# slow_clock.net
KiCad netlist of a schematic drawn in EAGLE
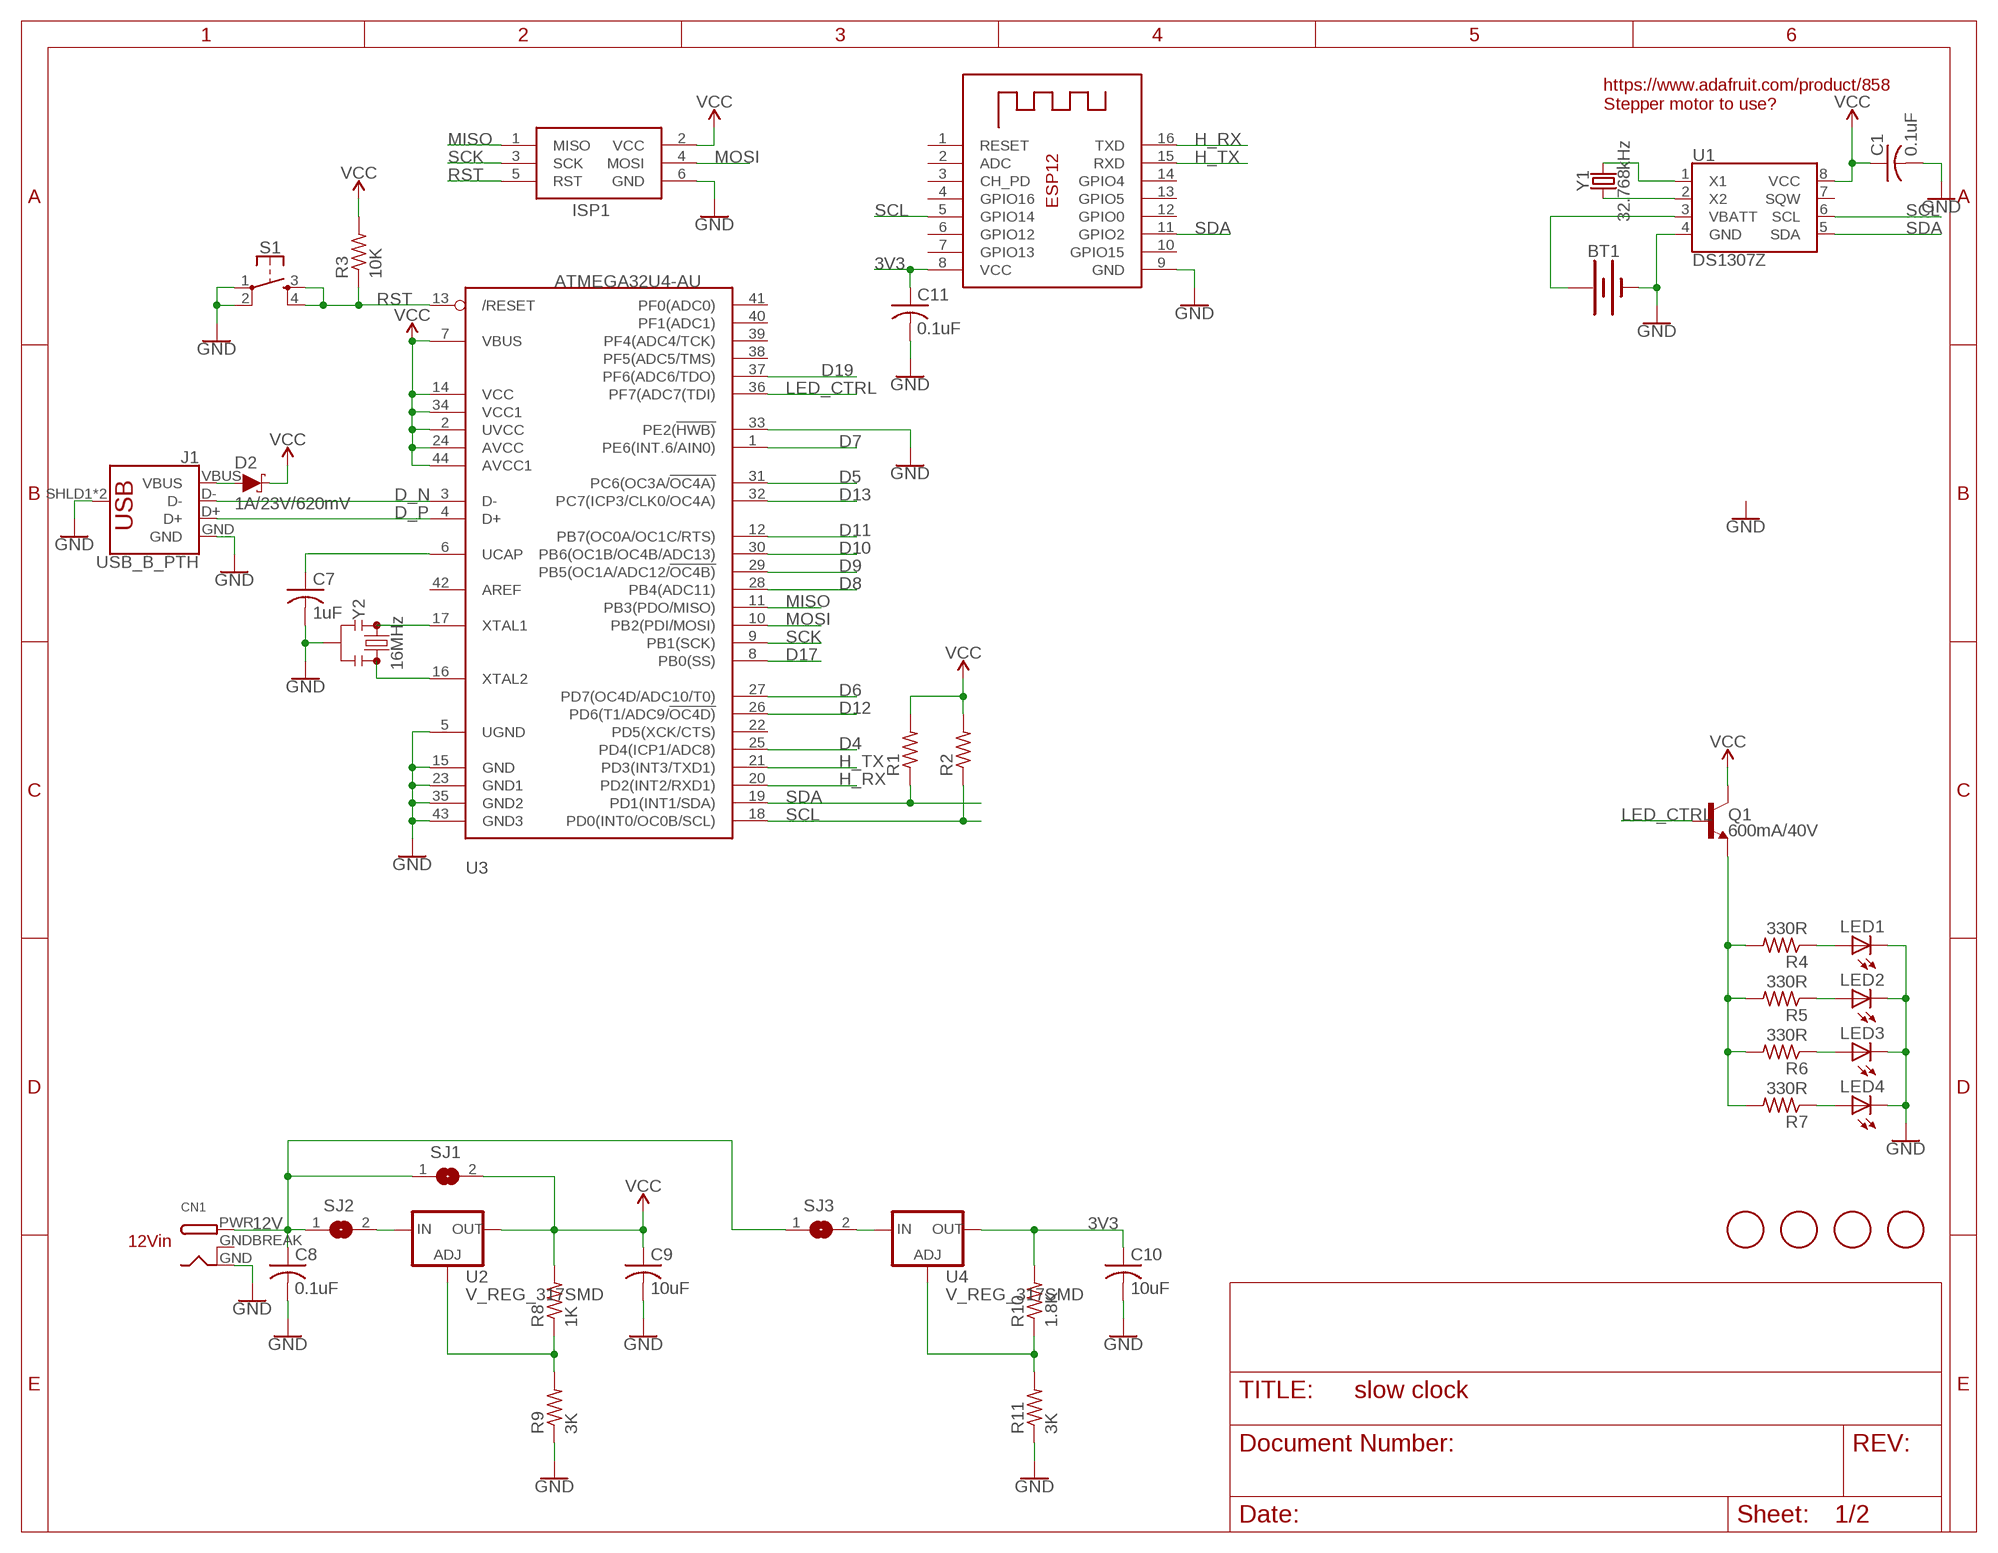
[diagram p0: schematic, sheet 1]
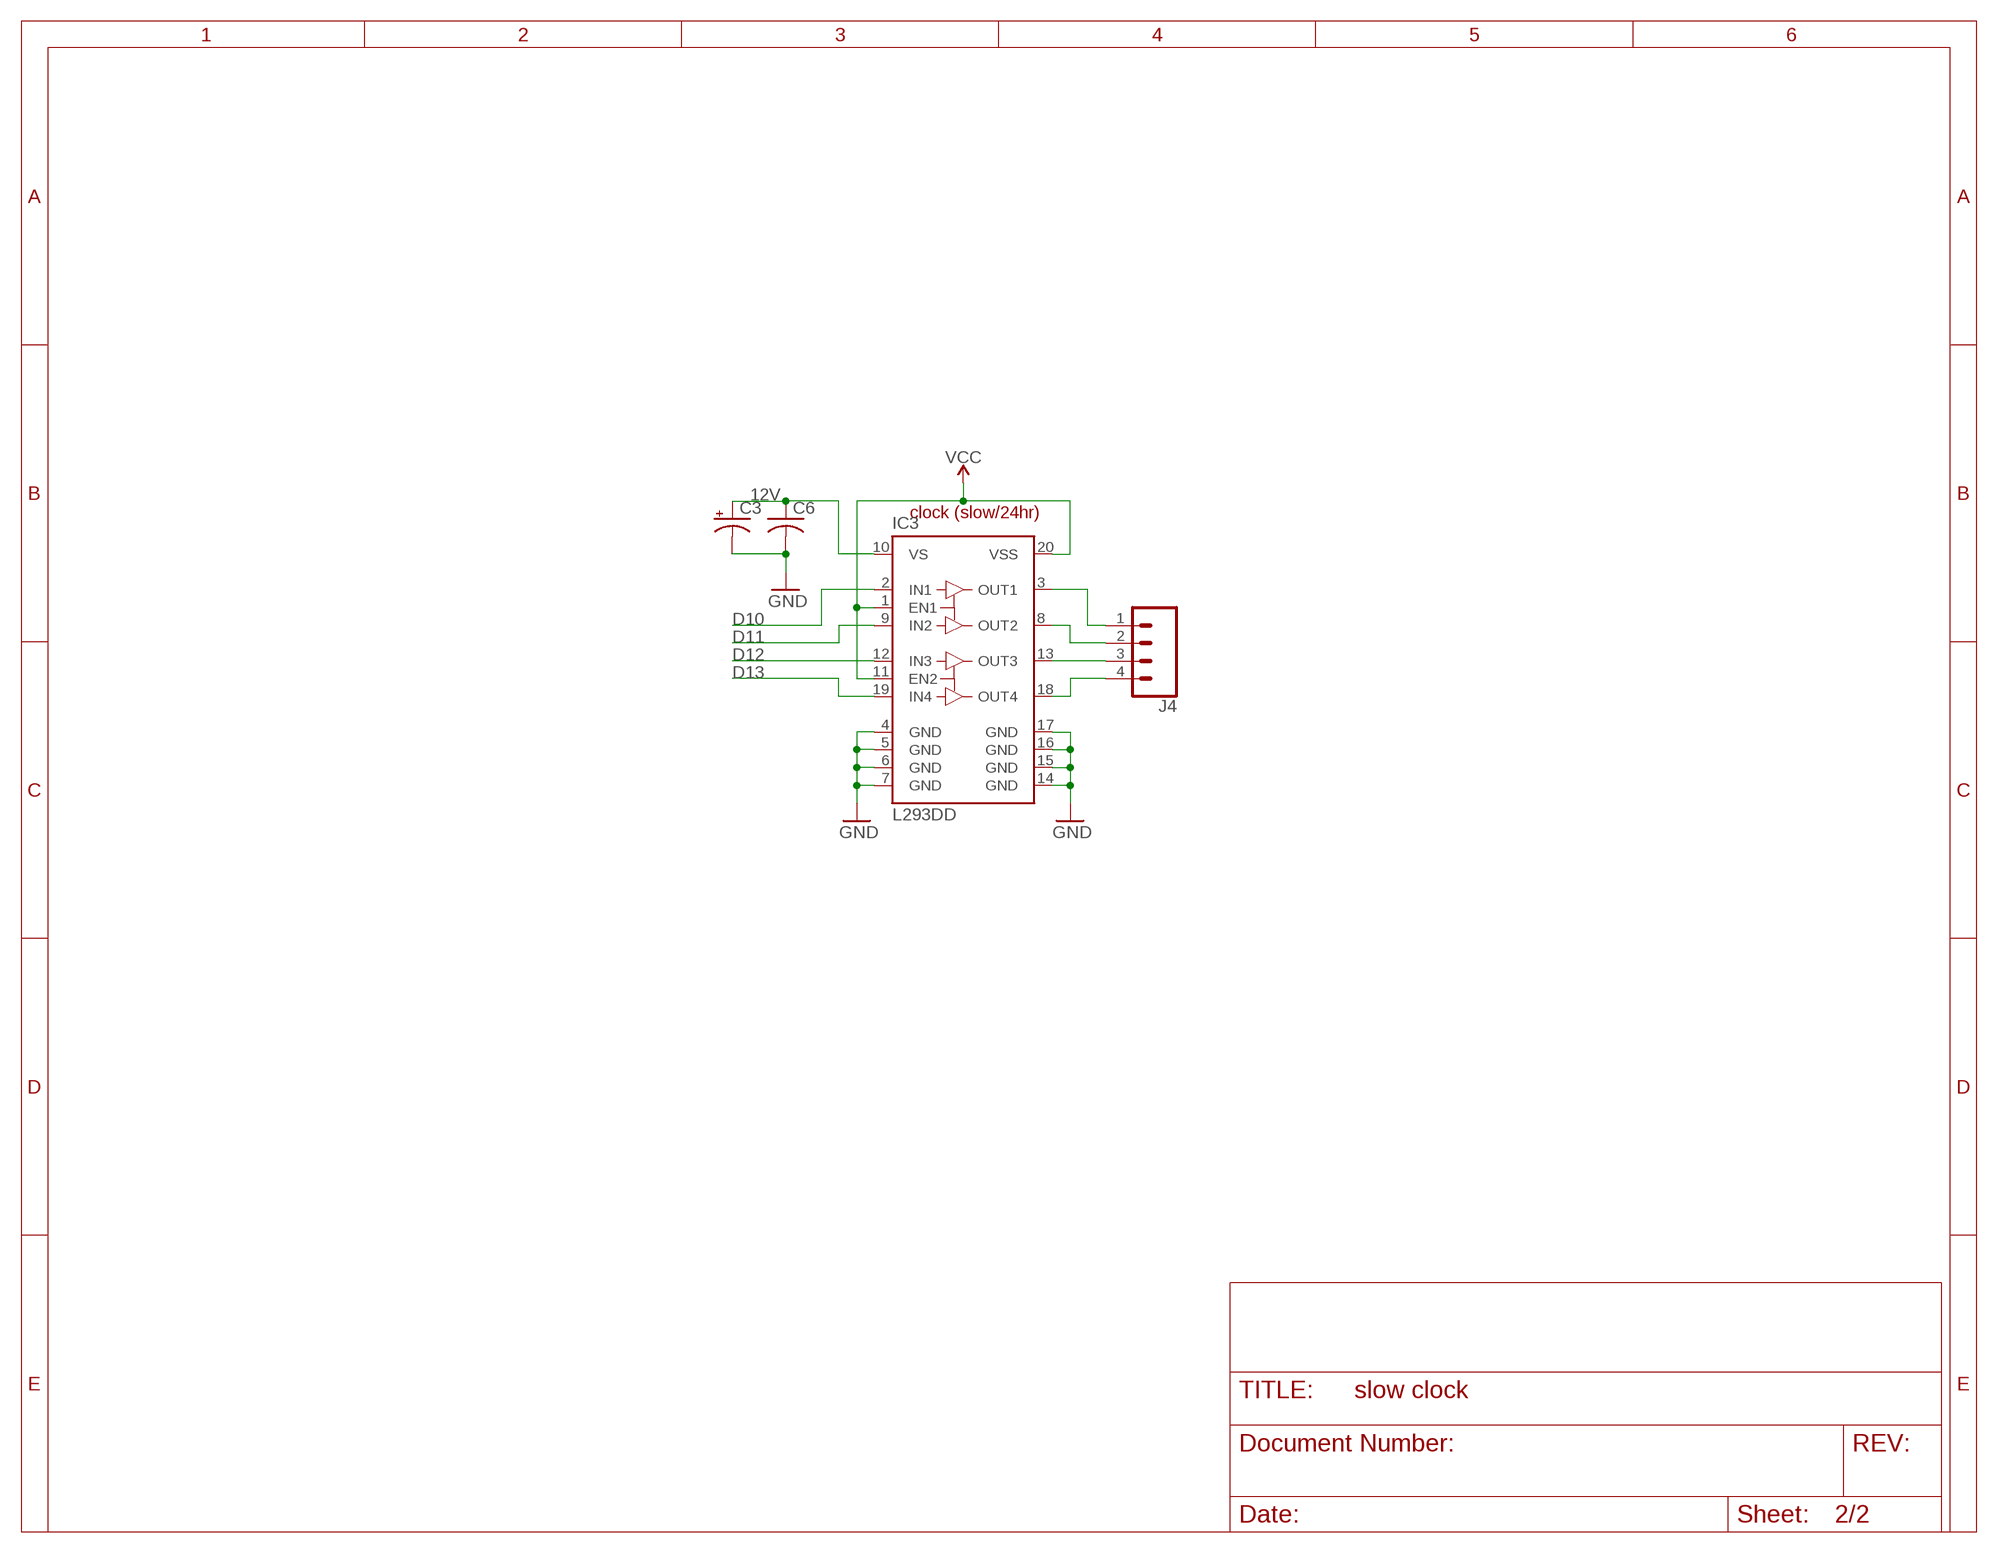
[diagram p1: schematic, sheet 2]

(export (version "E")
  (design (tool "Eeschema 10.0.6"))
  (components
    (comp (ref "C3")
      (value "CPOL-USD")
      (footprint "eagle-import:PANASONIC_D")
      (libsource (lib "eagle-import") (part "CPOL-USD"))
    )
    (comp (ref "C6")
      (value "C-USC0805")
      (footprint "eagle-import:C0805")
      (libsource (lib "eagle-import") (part "C-USC0805"))
    )
    (comp (ref "IC3")
      (value "L293DD")
      (footprint "eagle-import:SO20")
      (libsource (lib "eagle-import") (part "L293DD"))
    )
    (comp (ref "J4")
      (value "CONN_04LOCK")
      (footprint "eagle-import:1X04_LOCK")
      (libsource (lib "eagle-import") (part "CONN_04LOCK"))
    )
    (comp (ref "BT1")
      (value "BATTERY-12MM_SMD")
      (footprint "eagle-import:BATTCON_12MM")
      (libsource (lib "eagle-import") (part "BATTERY-12MM_SMD"))
    )
    (comp (ref "C1")
      (value "0.1uF")
      (footprint "eagle-import:C0805")
      (libsource (lib "eagle-import") (part "C-USC0805"))
    )
    (comp (ref "C7")
      (value "1uF")
      (footprint "eagle-import:C0805")
      (libsource (lib "eagle-import") (part "C-USC0805"))
    )
    (comp (ref "C8")
      (value "0.1uF")
      (footprint "eagle-import:C0805")
      (libsource (lib "eagle-import") (part "C-USC0805"))
    )
    (comp (ref "C9")
      (value "10uF")
      (footprint "eagle-import:C0805")
      (libsource (lib "eagle-import") (part "C-USC0805"))
    )
    (comp (ref "C10")
      (value "10uF")
      (footprint "eagle-import:C0805")
      (libsource (lib "eagle-import") (part "C-USC0805"))
    )
    (comp (ref "C11")
      (value "0.1uF")
      (footprint "eagle-import:C0805")
      (libsource (lib "eagle-import") (part "C-USC0805"))
    )
    (comp (ref "CN1")
      (value "DCBARRELPTH")
      (footprint "eagle-import:DCJACK_2MM_PTH")
      (libsource (lib "eagle-import") (part "DCBARRELPTH"))
    )
    (comp (ref "D2")
      (value "1A/23V/620mV")
      (footprint "eagle-import:SOD-323")
      (libsource (lib "eagle-import") (part "DIODE-SCHOTTKY-BAT20J"))
    )
    (comp (ref "ISP1")
      (value "AVRISP-6")
      (footprint "eagle-import:AVRISP")
      (libsource (lib "eagle-import") (part "AVRISP-6"))
    )
    (comp (ref "J1")
      (value "USB_B_PTH")
      (footprint "eagle-import:USB-B-PTH")
      (libsource (lib "eagle-import") (part "USB_B_PTH"))
    )
    (comp (ref "LED1")
      (value "LEDCHIPLED_0805")
      (footprint "eagle-import:CHIPLED_0805")
      (libsource (lib "eagle-import") (part "LEDCHIPLED_0805"))
    )
    (comp (ref "LED2")
      (value "LEDCHIPLED_0805")
      (footprint "eagle-import:CHIPLED_0805")
      (libsource (lib "eagle-import") (part "LEDCHIPLED_0805"))
    )
    (comp (ref "LED3")
      (value "LEDCHIPLED_0805")
      (footprint "eagle-import:CHIPLED_0805")
      (libsource (lib "eagle-import") (part "LEDCHIPLED_0805"))
    )
    (comp (ref "LED4")
      (value "LEDCHIPLED_0805")
      (footprint "eagle-import:CHIPLED_0805")
      (libsource (lib "eagle-import") (part "LEDCHIPLED_0805"))
    )
    (comp (ref "Q1")
      (value "600mA/40V")
      (footprint "eagle-import:SOT23-3")
      (libsource (lib "eagle-import") (part "TRANS_NPN-MMBT2222AL"))
    )
    (comp (ref "R1")
      (value "R-US_R0805")
      (footprint "eagle-import:R0805")
      (libsource (lib "eagle-import") (part "R-US_R0805"))
    )
    (comp (ref "R2")
      (value "R-US_R0805")
      (footprint "eagle-import:R0805")
      (libsource (lib "eagle-import") (part "R-US_R0805"))
    )
    (comp (ref "R3")
      (value "10K")
      (footprint "eagle-import:R0805")
      (libsource (lib "eagle-import") (part "R-US_R0805"))
    )
    (comp (ref "R4")
      (value "330R")
      (footprint "eagle-import:R0805")
      (libsource (lib "eagle-import") (part "R-US_R0805"))
    )
    (comp (ref "R5")
      (value "330R")
      (footprint "eagle-import:R0805")
      (libsource (lib "eagle-import") (part "R-US_R0805"))
    )
    (comp (ref "R6")
      (value "330R")
      (footprint "eagle-import:R0805")
      (libsource (lib "eagle-import") (part "R-US_R0805"))
    )
    (comp (ref "R7")
      (value "330R")
      (footprint "eagle-import:R0805")
      (libsource (lib "eagle-import") (part "R-US_R0805"))
    )
    (comp (ref "R8")
      (value "1K")
      (footprint "eagle-import:R0805")
      (libsource (lib "eagle-import") (part "R-US_R0805"))
    )
    (comp (ref "R9")
      (value "3K")
      (footprint "eagle-import:R0805")
      (libsource (lib "eagle-import") (part "R-US_R0805"))
    )
    (comp (ref "R10")
      (value "1.8K")
      (footprint "eagle-import:R0805")
      (libsource (lib "eagle-import") (part "R-US_R0805"))
    )
    (comp (ref "R11")
      (value "3K")
      (footprint "eagle-import:R0805")
      (libsource (lib "eagle-import") (part "R-US_R0805"))
    )
    (comp (ref "S1")
      (value "MOMENTARY-SWITCH-SPST-2-SMD-5.2MM")
      (footprint "eagle-import:TACTILE_SWITCH_SMD_5.2MM")
      (libsource (lib "eagle-import") (part "MOMENTARY-SWITCH-SPST-2-SMD-5.2MM"))
    )
    (comp (ref "SJ1") (value "SJ") (footprint "eagle-import:SJ") (libsource (lib "eagle-import") (part "SJ")))
    (comp (ref "SJ2") (value "SJ") (footprint "eagle-import:SJ") (libsource (lib "eagle-import") (part "SJ")))
    (comp (ref "SJ3") (value "SJ") (footprint "eagle-import:SJ") (libsource (lib "eagle-import") (part "SJ")))
    (comp (ref "U$2")
      (value "FIDUCIAL")
      (footprint "eagle-import:FIDUCIAL_1MM")
      (libsource (lib "eagle-import") (part "FIDUCIAL"))
    )
    (comp (ref "U$3")
      (value "FIDUCIAL")
      (footprint "eagle-import:FIDUCIAL_1MM")
      (libsource (lib "eagle-import") (part "FIDUCIAL"))
    )
    (comp (ref "U$4")
      (value "FIDUCIAL")
      (footprint "eagle-import:FIDUCIAL_1MM")
      (libsource (lib "eagle-import") (part "FIDUCIAL"))
    )
    (comp (ref "U$5")
      (value "FIDUCIAL")
      (footprint "eagle-import:FIDUCIAL_1MM")
      (libsource (lib "eagle-import") (part "FIDUCIAL"))
    )
    (comp (ref "U1")
      (value "DS1307Z")
      (footprint "eagle-import:SO08-0.15")
      (libsource (lib "eagle-import") (part "DS1307Z"))
    )
    (comp (ref "U2")
      (value "V_REG_317SMD")
      (footprint "eagle-import:SOT223")
      (libsource (lib "eagle-import") (part "V_REG_317SMD"))
    )
    (comp (ref "U3")
      (value "ATMEGA32U4-AU")
      (footprint "eagle-import:TQFP44")
      (libsource (lib "eagle-import") (part "ATMEGA32U4-AU"))
    )
    (comp (ref "U4")
      (value "V_REG_317SMD")
      (footprint "eagle-import:SOT223")
      (libsource (lib "eagle-import") (part "V_REG_317SMD"))
    )
    (comp (ref "X1")
      (value "ESP-12")
      (footprint "eagle-import:ESP-12")
      (libsource (lib "eagle-import") (part "ESP-12"))
    )
    (comp (ref "Y1")
      (value "32.768kHz")
      (footprint "eagle-import:CRYSTAL-PTH-2X6-CYL-KIT")
      (libsource (lib "eagle-import") (part "CRYSTAL-32.768KHZPTH-2X6-KIT"))
    )
    (comp (ref "Y2")
      (value "16MHz")
      (footprint "eagle-import:RESONATOR-SMD-3.2X1.3")
      (libsource (lib "eagle-import") (part "RESONATOR-16MHZSMD_3.2X1.3"))
    )
  )
  (nets
    (net (code "1") (name "3V3") (class "Default")
      (node (ref "C10") (pin "1") (pinfunction "1_1") (pintype "passive"))
      (node (ref "C11") (pin "1") (pinfunction "1_1") (pintype "passive"))
      (node (ref "R10") (pin "2") (pinfunction "2_2") (pintype "passive"))
      (node (ref "U4") (pin "2") (pinfunction "OUT_2") (pintype "output"))
      (node (ref "X1") (pin "8") (pinfunction "VCC_8") (pintype "power_in"))
    )
    (net (code "2") (name "12V") (class "Default")
      (node (ref "C3") (pin "+") (pinfunction "+_+") (pintype "passive"))
      (node (ref "C6") (pin "1") (pinfunction "1_1") (pintype "passive"))
      (node (ref "C8") (pin "1") (pinfunction "1_1") (pintype "passive"))
      (node (ref "CN1") (pin "PWR") (pinfunction "PWR_PWR") (pintype "power_in"))
      (node (ref "IC3") (pin "10") (pinfunction "VS_10") (pintype "power_in"))
      (node (ref "SJ1") (pin "1") (pinfunction "1_1") (pintype "passive"))
      (node (ref "SJ2") (pin "1") (pinfunction "1_1") (pintype "passive"))
      (node (ref "SJ3") (pin "1") (pinfunction "1_1") (pintype "passive"))
    )
    (net (code "3") (name "D4") (class "Default")
      (node (ref "U3") (pin "25") (pinfunction "PD4(ICP1/ADC8)_25") (pintype "bidirectional"))
    )
    (net (code "4") (name "D5") (class "Default")
      (node (ref "U3") (pin "31") (pinfunction "PC6(OC3A/~{OC4A})_31") (pintype "bidirectional"))
    )
    (net (code "5") (name "D6") (class "Default")
      (node (ref "U3") (pin "27") (pinfunction "PD7(OC4D/ADC10/T0)_27") (pintype "bidirectional"))
    )
    (net (code "6") (name "D7") (class "Default")
      (node (ref "U3") (pin "1") (pinfunction "PE6(INT.6/AIN0)_1") (pintype "bidirectional"))
    )
    (net (code "7") (name "D8") (class "Default")
      (node (ref "U3") (pin "28") (pinfunction "PB4(ADC11)_28") (pintype "bidirectional"))
    )
    (net (code "8") (name "D9") (class "Default")
      (node (ref "U3") (pin "29") (pinfunction "PB5(OC1A/ADC12/~{OC4B})_29") (pintype "bidirectional"))
    )
    (net (code "9") (name "D10") (class "Default")
      (node (ref "IC3") (pin "2") (pinfunction "IN1_2") (pintype "input"))
      (node (ref "U3") (pin "30") (pinfunction "PB6(OC1B/OC4B/ADC13)_30") (pintype "bidirectional"))
    )
    (net (code "10") (name "D11") (class "Default")
      (node (ref "IC3") (pin "9") (pinfunction "IN2_9") (pintype "input"))
      (node (ref "U3") (pin "12") (pinfunction "PB7(OC0A/OC1C/RTS)_12") (pintype "bidirectional"))
    )
    (net (code "11") (name "D12") (class "Default")
      (node (ref "IC3") (pin "12") (pinfunction "IN3_12") (pintype "input"))
      (node (ref "U3") (pin "26") (pinfunction "PD6(T1/ADC9/~{OC4D})_26") (pintype "bidirectional"))
    )
    (net (code "12") (name "D13") (class "Default")
      (node (ref "IC3") (pin "19") (pinfunction "IN4_19") (pintype "input"))
      (node (ref "U3") (pin "32") (pinfunction "PC7(ICP3/CLK0/OC4A)_32") (pintype "bidirectional"))
    )
    (net (code "13") (name "D17") (class "Default")
      (node (ref "U3") (pin "8") (pinfunction "PB0(SS)_8") (pintype "bidirectional"))
    )
    (net (code "14") (name "D19") (class "Default")
      (node (ref "U3") (pin "37") (pinfunction "PF6(ADC6/TDO)_37") (pintype "bidirectional"))
    )
    (net (code "15") (name "D_N") (class "Default")
      (node (ref "J1") (pin "D-") (pinfunction "D-_D-") (pintype "bidirectional"))
      (node (ref "U3") (pin "3") (pinfunction "D-_3") (pintype "bidirectional"))
    )
    (net (code "16") (name "D_P") (class "Default")
      (node (ref "J1") (pin "D+") (pinfunction "D+_D+") (pintype "bidirectional"))
      (node (ref "U3") (pin "4") (pinfunction "D+_4") (pintype "bidirectional"))
    )
    (net (code "17") (name "GND") (class "Default")
      (node (ref "BT1") (pin "GND") (pinfunction "-_GND") (pintype "power_in"))
      (node (ref "C1") (pin "2") (pinfunction "2_2") (pintype "passive"))
      (node (ref "C10") (pin "2") (pinfunction "2_2") (pintype "passive"))
      (node (ref "C11") (pin "2") (pinfunction "2_2") (pintype "passive"))
      (node (ref "C3") (pin "-") (pinfunction "-_-") (pintype "passive"))
      (node (ref "C6") (pin "2") (pinfunction "2_2") (pintype "passive"))
      (node (ref "C7") (pin "2") (pinfunction "2_2") (pintype "passive"))
      (node (ref "C8") (pin "2") (pinfunction "2_2") (pintype "passive"))
      (node (ref "C9") (pin "2") (pinfunction "2_2") (pintype "passive"))
      (node (ref "CN1") (pin "GND") (pinfunction "GND_GND") (pintype "power_in"))
      (node (ref "IC3") (pin "14") (pinfunction "GND_14") (pintype "power_in"))
      (node (ref "IC3") (pin "15") (pinfunction "GND_15") (pintype "power_in"))
      (node (ref "IC3") (pin "16") (pinfunction "GND_16") (pintype "power_in"))
      (node (ref "IC3") (pin "17") (pinfunction "GND_17") (pintype "power_in"))
      (node (ref "IC3") (pin "4") (pinfunction "GND_4") (pintype "power_in"))
      (node (ref "IC3") (pin "5") (pinfunction "GND_5") (pintype "power_in"))
      (node (ref "IC3") (pin "6") (pinfunction "GND_6") (pintype "power_in"))
      (node (ref "IC3") (pin "7") (pinfunction "GND_7") (pintype "power_in"))
      (node (ref "ISP1") (pin "6") (pinfunction "GND_6") (pintype "power_in"))
      (node (ref "J1") (pin "GND") (pinfunction "GND_GND") (pintype "power_in"))
      (node (ref "J1") (pin "SHLD1") (pinfunction "SHIELD_SHLD1") (pintype "bidirectional"))
      (node (ref "J1") (pin "SHLD2") (pinfunction "SHIELD_SHLD2") (pintype "bidirectional"))
      (node (ref "LED1") (pin "C") (pinfunction "C_C") (pintype "passive"))
      (node (ref "LED2") (pin "C") (pinfunction "C_C") (pintype "passive"))
      (node (ref "LED3") (pin "C") (pinfunction "C_C") (pintype "passive"))
      (node (ref "LED4") (pin "C") (pinfunction "C_C") (pintype "passive"))
      (node (ref "R11") (pin "1") (pinfunction "1_1") (pintype "passive"))
      (node (ref "R9") (pin "1") (pinfunction "1_1") (pintype "passive"))
      (node (ref "S1") (pin "1") (pinfunction "1_1") (pintype "passive"))
      (node (ref "S1") (pin "2") (pinfunction "2_2") (pintype "passive"))
      (node (ref "U1") (pin "4") (pinfunction "GND_4") (pintype "bidirectional"))
      (node (ref "U3") (pin "15") (pinfunction "GND_15") (pintype "bidirectional"))
      (node (ref "U3") (pin "23") (pinfunction "GND1_23") (pintype "bidirectional"))
      (node (ref "U3") (pin "33") (pinfunction "PE2(~{HWB})_33") (pintype "bidirectional"))
      (node (ref "U3") (pin "35") (pinfunction "GND2_35") (pintype "bidirectional"))
      (node (ref "U3") (pin "43") (pinfunction "GND3_43") (pintype "bidirectional"))
      (node (ref "U3") (pin "5") (pinfunction "UGND_5") (pintype "bidirectional"))
      (node (ref "X1") (pin "9") (pinfunction "GND_9") (pintype "power_in"))
      (node (ref "Y2") (pin "2") (pinfunction "2_2") (pintype "passive"))
    )
    (net (code "18") (name "GNDBREAK") (class "Default")
      (node (ref "CN1") (pin "GNDBREAK") (pinfunction "GNDBREAK_GNDBREAK") (pintype "power_in"))
    )
    (net (code "19") (name "H_RX") (class "Default")
      (node (ref "U3") (pin "20") (pinfunction "PD2(INT2/RXD1)_20") (pintype "bidirectional"))
      (node (ref "X1") (pin "16") (pinfunction "TXD_16") (pintype "output"))
    )
    (net (code "20") (name "H_TX") (class "Default")
      (node (ref "U3") (pin "21") (pinfunction "PD3(INT3/TXD1)_21") (pintype "bidirectional"))
      (node (ref "X1") (pin "15") (pinfunction "RXD_15") (pintype "input"))
    )
    (net (code "21") (name "LED_CTRL") (class "Default")
      (node (ref "Q1") (pin "1") (pinfunction "B_1") (pintype "passive"))
      (node (ref "U3") (pin "36") (pinfunction "PF7(ADC7(TDI)_36") (pintype "bidirectional"))
    )
    (net (code "22") (name "MISO") (class "Default")
      (node (ref "ISP1") (pin "1") (pinfunction "MISO_1") (pintype "input"))
      (node (ref "U3") (pin "11") (pinfunction "PB3(PDO/MISO)_11") (pintype "bidirectional"))
    )
    (net (code "23") (name "MOSI") (class "Default")
      (node (ref "ISP1") (pin "4") (pinfunction "MOSI_4") (pintype "output"))
      (node (ref "U3") (pin "10") (pinfunction "PB2(PDI/MOSI)_10") (pintype "bidirectional"))
    )
    (net (code "24") (name "Net-(BT1-+)") (class "Default")
      (node (ref "BT1") (pin "PWR@1") (pinfunction "+_PWR@1") (pintype "power_in"))
      (node (ref "U1") (pin "3") (pinfunction "VBATT_3") (pintype "bidirectional"))
    )
    (net (code "25") (name "Net-(D2-PadA)") (class "Default")
      (node (ref "D2") (pin "A") (pinfunction "A_A") (pintype "passive"))
      (node (ref "J1") (pin "VBUS") (pinfunction "VBUS_VBUS") (pintype "power_in"))
    )
    (net (code "26") (name "Net-(IC3-OUT1)") (class "Default")
      (node (ref "IC3") (pin "3") (pinfunction "OUT1_3") (pintype "output"))
      (node (ref "J4") (pin "1") (pinfunction "1_1") (pintype "passive"))
    )
    (net (code "27") (name "Net-(IC3-OUT2)") (class "Default")
      (node (ref "IC3") (pin "8") (pinfunction "OUT2_8") (pintype "output"))
      (node (ref "J4") (pin "2") (pinfunction "2_2") (pintype "passive"))
    )
    (net (code "28") (name "Net-(IC3-OUT3)") (class "Default")
      (node (ref "IC3") (pin "13") (pinfunction "OUT3_13") (pintype "output"))
      (node (ref "J4") (pin "3") (pinfunction "3_3") (pintype "passive"))
    )
    (net (code "29") (name "Net-(IC3-OUT4)") (class "Default")
      (node (ref "IC3") (pin "18") (pinfunction "OUT4_18") (pintype "output"))
      (node (ref "J4") (pin "4") (pinfunction "4_4") (pintype "passive"))
    )
    (net (code "30") (name "Net-(LED1-PadA)") (class "Default")
      (node (ref "LED1") (pin "A") (pinfunction "A_A") (pintype "passive"))
      (node (ref "R4") (pin "1") (pinfunction "1_1") (pintype "passive"))
    )
    (net (code "31") (name "Net-(LED2-PadA)") (class "Default")
      (node (ref "LED2") (pin "A") (pinfunction "A_A") (pintype "passive"))
      (node (ref "R5") (pin "1") (pinfunction "1_1") (pintype "passive"))
    )
    (net (code "32") (name "Net-(LED3-PadA)") (class "Default")
      (node (ref "LED3") (pin "A") (pinfunction "A_A") (pintype "passive"))
      (node (ref "R6") (pin "1") (pinfunction "1_1") (pintype "passive"))
    )
    (net (code "33") (name "Net-(LED4-PadA)") (class "Default")
      (node (ref "LED4") (pin "A") (pinfunction "A_A") (pintype "passive"))
      (node (ref "R7") (pin "1") (pinfunction "1_1") (pintype "passive"))
    )
    (net (code "34") (name "Net-(Q1-E)") (class "Default")
      (node (ref "Q1") (pin "2") (pinfunction "E_2") (pintype "passive"))
      (node (ref "R4") (pin "2") (pinfunction "2_2") (pintype "passive"))
      (node (ref "R5") (pin "2") (pinfunction "2_2") (pintype "passive"))
      (node (ref "R6") (pin "2") (pinfunction "2_2") (pintype "passive"))
      (node (ref "R7") (pin "2") (pinfunction "2_2") (pintype "passive"))
    )
    (net (code "35") (name "Net-(U1-X1)") (class "Default")
      (node (ref "U1") (pin "1") (pinfunction "X1_1") (pintype "bidirectional"))
      (node (ref "Y1") (pin "2") (pinfunction "2_2") (pintype "passive"))
    )
    (net (code "36") (name "Net-(U1-X2)") (class "Default")
      (node (ref "U1") (pin "2") (pinfunction "X2_2") (pintype "bidirectional"))
      (node (ref "Y1") (pin "1") (pinfunction "1_1") (pintype "passive"))
    )
    (net (code "37") (name "Net-(U2-ADJ)") (class "Default")
      (node (ref "R8") (pin "1") (pinfunction "1_1") (pintype "passive"))
      (node (ref "R9") (pin "2") (pinfunction "2_2") (pintype "passive"))
      (node (ref "U2") (pin "1") (pinfunction "ADJ_1") (pintype "input"))
    )
    (net (code "38") (name "Net-(U2-IN)") (class "Default")
      (node (ref "SJ2") (pin "2") (pinfunction "2_2") (pintype "passive"))
      (node (ref "U2") (pin "3") (pinfunction "IN_3") (pintype "input"))
    )
    (net (code "39") (name "Net-(U3-UCAP)") (class "Default")
      (node (ref "C7") (pin "1") (pinfunction "1_1") (pintype "passive"))
      (node (ref "U3") (pin "6") (pinfunction "UCAP_6") (pintype "bidirectional"))
    )
    (net (code "40") (name "Net-(U3-XTAL1)") (class "Default")
      (node (ref "U3") (pin "17") (pinfunction "XTAL1_17") (pintype "bidirectional"))
      (node (ref "Y2") (pin "1") (pinfunction "1_1") (pintype "passive"))
    )
    (net (code "41") (name "Net-(U3-XTAL2)") (class "Default")
      (node (ref "U3") (pin "16") (pinfunction "XTAL2_16") (pintype "bidirectional"))
      (node (ref "Y2") (pin "3") (pinfunction "3_3") (pintype "passive"))
    )
    (net (code "42") (name "Net-(U4-ADJ)") (class "Default")
      (node (ref "R10") (pin "1") (pinfunction "1_1") (pintype "passive"))
      (node (ref "R11") (pin "2") (pinfunction "2_2") (pintype "passive"))
      (node (ref "U4") (pin "1") (pinfunction "ADJ_1") (pintype "input"))
    )
    (net (code "43") (name "Net-(U4-IN)") (class "Default")
      (node (ref "SJ3") (pin "2") (pinfunction "2_2") (pintype "passive"))
      (node (ref "U4") (pin "3") (pinfunction "IN_3") (pintype "input"))
    )
    (net (code "44") (name "RST") (class "Default")
      (node (ref "ISP1") (pin "5") (pinfunction "RST_5") (pintype "output"))
      (node (ref "R3") (pin "1") (pinfunction "1_1") (pintype "passive"))
      (node (ref "S1") (pin "3") (pinfunction "3_3") (pintype "passive"))
      (node (ref "S1") (pin "4") (pinfunction "4_4") (pintype "passive"))
      (node (ref "U3") (pin "13") (pinfunction "/RESET_13") (pintype "bidirectional"))
    )
    (net (code "45") (name "SCK") (class "Default")
      (node (ref "ISP1") (pin "3") (pinfunction "SCK_3") (pintype "output"))
      (node (ref "U3") (pin "9") (pinfunction "PB1(SCK)_9") (pintype "bidirectional"))
    )
    (net (code "46") (name "SCL") (class "Default")
      (node (ref "R2") (pin "1") (pinfunction "1_1") (pintype "passive"))
      (node (ref "U1") (pin "6") (pinfunction "SCL_6") (pintype "bidirectional"))
      (node (ref "U3") (pin "18") (pinfunction "PD0(INT0/OC0B/SCL)_18") (pintype "bidirectional"))
      (node (ref "X1") (pin "5") (pinfunction "GPIO14_5") (pintype "bidirectional"))
    )
    (net (code "47") (name "SDA") (class "Default")
      (node (ref "R1") (pin "1") (pinfunction "1_1") (pintype "passive"))
      (node (ref "U1") (pin "5") (pinfunction "SDA_5") (pintype "bidirectional"))
      (node (ref "U3") (pin "19") (pinfunction "PD1(INT1/SDA)_19") (pintype "bidirectional"))
      (node (ref "X1") (pin "11") (pinfunction "GPIO2_11") (pintype "bidirectional"))
    )
    (net (code "48") (name "VCC") (class "Default")
      (node (ref "C1") (pin "1") (pinfunction "1_1") (pintype "passive"))
      (node (ref "C9") (pin "1") (pinfunction "1_1") (pintype "passive"))
      (node (ref "D2") (pin "C") (pinfunction "C_C") (pintype "passive"))
      (node (ref "IC3") (pin "1") (pinfunction "EN1_1") (pintype "input"))
      (node (ref "IC3") (pin "11") (pinfunction "EN2_11") (pintype "input"))
      (node (ref "IC3") (pin "20") (pinfunction "VSS_20") (pintype "power_in"))
      (node (ref "ISP1") (pin "2") (pinfunction "VCC_2") (pintype "power_in"))
      (node (ref "Q1") (pin "3") (pinfunction "C_3") (pintype "passive"))
      (node (ref "R1") (pin "2") (pinfunction "2_2") (pintype "passive"))
      (node (ref "R2") (pin "2") (pinfunction "2_2") (pintype "passive"))
      (node (ref "R3") (pin "2") (pinfunction "2_2") (pintype "passive"))
      (node (ref "R8") (pin "2") (pinfunction "2_2") (pintype "passive"))
      (node (ref "SJ1") (pin "2") (pinfunction "2_2") (pintype "passive"))
      (node (ref "U1") (pin "8") (pinfunction "VCC_8") (pintype "bidirectional"))
      (node (ref "U2") (pin "2") (pinfunction "OUT_2") (pintype "output"))
      (node (ref "U3") (pin "14") (pinfunction "VCC_14") (pintype "bidirectional"))
      (node (ref "U3") (pin "2") (pinfunction "UVCC_2") (pintype "bidirectional"))
      (node (ref "U3") (pin "24") (pinfunction "AVCC_24") (pintype "bidirectional"))
      (node (ref "U3") (pin "34") (pinfunction "VCC1_34") (pintype "bidirectional"))
      (node (ref "U3") (pin "44") (pinfunction "AVCC1_44") (pintype "bidirectional"))
      (node (ref "U3") (pin "7") (pinfunction "VBUS_7") (pintype "bidirectional"))
    )
    (net (code "49") (name "unconnected-(U1-SQW-Pad7)") (class "Default")
      (node (ref "U1") (pin "7") (pinfunction "SQW_7") (pintype "bidirectional"))
    )
    (net (code "50") (name "unconnected-(U3-AREF-Pad42)") (class "Default")
      (node (ref "U3") (pin "42") (pinfunction "AREF_42") (pintype "bidirectional"))
    )
    (net (code "51") (name "unconnected-(U3-PD5(XCK{slash}CTS)-Pad22)") (class "Default")
      (node (ref "U3") (pin "22") (pinfunction "PD5(XCK/CTS)_22") (pintype "bidirectional"))
    )
    (net (code "52") (name "unconnected-(U3-PF0(ADC0)-Pad41)") (class "Default")
      (node (ref "U3") (pin "41") (pinfunction "PF0(ADC0)_41") (pintype "bidirectional"))
    )
    (net (code "53") (name "unconnected-(U3-PF1(ADC1)-Pad40)") (class "Default")
      (node (ref "U3") (pin "40") (pinfunction "PF1(ADC1)_40") (pintype "bidirectional"))
    )
    (net (code "54") (name "unconnected-(U3-PF4(ADC4{slash}TCK)-Pad39)") (class "Default")
      (node (ref "U3") (pin "39") (pinfunction "PF4(ADC4/TCK)_39") (pintype "bidirectional"))
    )
    (net (code "55") (name "unconnected-(U3-PF5(ADC5{slash}TMS)-Pad38)") (class "Default")
      (node (ref "U3") (pin "38") (pinfunction "PF5(ADC5/TMS)_38") (pintype "bidirectional"))
    )
    (net (code "56") (name "unconnected-(X1-ADC-Pad2)") (class "Default")
      (node (ref "X1") (pin "2") (pinfunction "ADC_2") (pintype "passive"))
    )
    (net (code "57") (name "unconnected-(X1-CH_PD-Pad3)") (class "Default")
      (node (ref "X1") (pin "3") (pinfunction "CH_PD_3") (pintype "input"))
    )
    (net (code "58") (name "unconnected-(X1-GPIO0-Pad12)") (class "Default")
      (node (ref "X1") (pin "12") (pinfunction "GPIO0_12") (pintype "bidirectional"))
    )
    (net (code "59") (name "unconnected-(X1-GPIO4-Pad14)") (class "Default")
      (node (ref "X1") (pin "14") (pinfunction "GPIO4_14") (pintype "bidirectional"))
    )
    (net (code "60") (name "unconnected-(X1-GPIO5-Pad13)") (class "Default")
      (node (ref "X1") (pin "13") (pinfunction "GPIO5_13") (pintype "bidirectional"))
    )
    (net (code "61") (name "unconnected-(X1-GPIO12-Pad6)") (class "Default")
      (node (ref "X1") (pin "6") (pinfunction "GPIO12_6") (pintype "bidirectional"))
    )
    (net (code "62") (name "unconnected-(X1-GPIO13-Pad7)") (class "Default")
      (node (ref "X1") (pin "7") (pinfunction "GPIO13_7") (pintype "bidirectional"))
    )
    (net (code "63") (name "unconnected-(X1-GPIO15-Pad10)") (class "Default")
      (node (ref "X1") (pin "10") (pinfunction "GPIO15_10") (pintype "bidirectional"))
    )
    (net (code "64") (name "unconnected-(X1-GPIO16-Pad4)") (class "Default")
      (node (ref "X1") (pin "4") (pinfunction "GPIO16_4") (pintype "bidirectional"))
    )
    (net (code "65") (name "unconnected-(X1-RESET-Pad1)") (class "Default")
      (node (ref "X1") (pin "1") (pinfunction "RESET_1") (pintype "input"))
    )
  )
)
